# Interfaz_RTC.net
KiCad netlist of a schematic drawn in Altium Designer
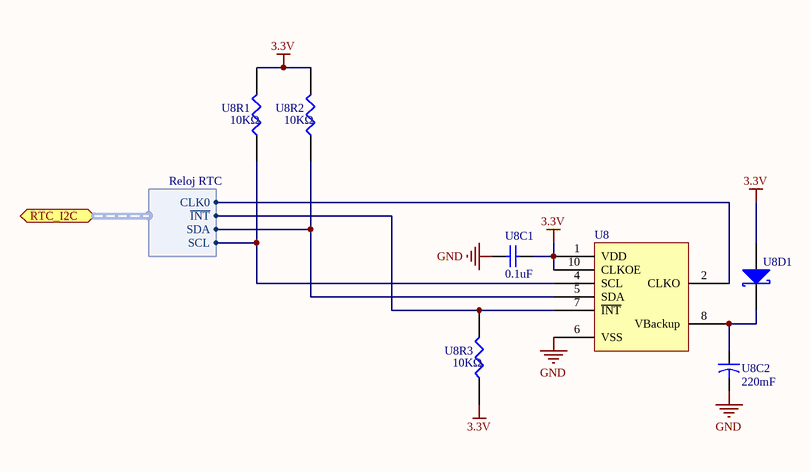
[diagram p0: Interfaz_RTC.SchDoc]

(export (version "E")
  (design (tool "Eeschema 10.0.6"))
  (components
    (comp (ref "U8")
      (value "~")
      (footprint "RV-3029-C2")
      (description "MICRO CRYSTAL - RV-3029-C2 OPTION B - REAL-TIME-CLOCK, SMD, I2C, 32.768KHZ")
      (fields
        (field (name "MANUFACTURER PART NUMBER") "RV-3029-C2")
        (field (name "MANUFACTURER") "Micro Crystal Switzerland")
      )
      (libsource (lib "EMLib1") (part "RV-3029-C2 B"))
    )
    (comp (ref "U8C1")
      (value "0.1uF")
      (footprint "0603 - CAP")
      (description "CAP CERAMIC 0.1UF, 25V, X7R, 0603")
      (fields
        (field (name "MANUFACTURER PART NUMBER") "CGJ3E2X7R1E104K080AA")
        (field (name "MANUFACTURER") "TDK Corporation")
      )
      (libsource (lib "*") (part "Cap"))
    )
    (comp (ref "U8C2")
      (value "220mF")
      (footprint "DSK-3R3H224U-HL")
      (description "CAP 220MF -20% +80% 3.3V SMD")
      (fields
        (field (name "MANUFACTURER") "Elna America")
        (field (name "MANUFACTURER PART NUMBER") "DSK-3R3H224U-HL")
      )
      (libsource (lib "Miscellaneous Devices") (part "Cap2"))
    )
    (comp (ref "U8D1")
      (value "NSR0320MW2T1G")
      (footprint "SOD-323")
      (description "DIODE SCHOTTKY 1A 20V SOD-323")
      (fields (field (name "MANUFACTURER") "On Semiconductor"))
      (libsource (lib "IR Discrete Rectifier - Schottky") (part "10MQ060N"))
    )
    (comp (ref "U8R1")
      (value "10KΩ")
      (footprint "0805-RES")
      (description "10 kOhms ±5% 0.125W, 1/8W Chip Resistor 0805")
      (fields
        (field (name "MANUFACTURER PART NUMBER") "RC0805JR-0710KL")
        (field (name "MANUFACTURER") "Yageo")
      )
      (libsource (lib "*") (part "RES1"))
    )
    (comp (ref "U8R2")
      (value "10KΩ")
      (footprint "0805-RES")
      (description "10 kOhms ±5% 0.125W, 1/8W Chip Resistor 0805")
      (fields
        (field (name "MANUFACTURER PART NUMBER") "RC0805JR-0710KL")
        (field (name "MANUFACTURER") "Yageo")
      )
      (libsource (lib "*") (part "RES1"))
    )
    (comp (ref "U8R3")
      (value "10KΩ")
      (footprint "0805-RES")
      (description "10 kOhms ±5% 0.125W, 1/8W Chip Resistor 0805")
      (fields
        (field (name "MANUFACTURER PART NUMBER") "RC0805JR-0710KL")
        (field (name "MANUFACTURER") "Yageo")
      )
      (libsource (lib "*") (part "RES1"))
    )
  )
  (nets
    (net (code "3") (name "/CLK0") (class "Default")
      (node (ref "U8") (pin "2") (pinfunction "CLKO_2") (pintype "passive"))
    )
    (net (code "4") (name "/SCL") (class "Default")
      (node (ref "U8") (pin "4") (pinfunction "SCL_4") (pintype "passive"))
      (node (ref "U8R1") (pin "1") (pinfunction "1_1") (pintype "passive"))
    )
    (net (code "5") (name "/SDA") (class "Default")
      (node (ref "U8") (pin "5") (pinfunction "SDA_5") (pintype "passive"))
      (node (ref "U8R2") (pin "1") (pinfunction "1_1") (pintype "passive"))
    )
    (net (code "7") (name "/~{INT}") (class "Default")
      (node (ref "U8") (pin "7") (pinfunction "~{INT}_7") (pintype "passive"))
      (node (ref "U8R3") (pin "2") (pinfunction "2_2") (pintype "passive"))
    )
    (net (code "8") (name "3.3V") (class "Default")
      (node (ref "U8") (pin "1") (pinfunction "VDD_1") (pintype "passive"))
      (node (ref "U8") (pin "10") (pinfunction "CLKOE_10") (pintype "passive"))
      (node (ref "U8C1") (pin "1") (pinfunction "1_1") (pintype "passive"))
      (node (ref "U8D1") (pin "1") (pinfunction "A_1") (pintype "passive"))
      (node (ref "U8R1") (pin "2") (pinfunction "2_2") (pintype "passive"))
      (node (ref "U8R2") (pin "2") (pinfunction "2_2") (pintype "passive"))
      (node (ref "U8R3") (pin "1") (pinfunction "1_1") (pintype "passive"))
    )
    (net (code "9") (name "GND") (class "Default")
      (node (ref "U8") (pin "6") (pinfunction "VSS_6") (pintype "passive"))
      (node (ref "U8C1") (pin "2") (pinfunction "2_2") (pintype "passive"))
      (node (ref "U8C2") (pin "2") (pinfunction "2_2") (pintype "passive"))
    )
    (net (code "10") (name "Net-(U8-VBackup)") (class "Default")
      (node (ref "U8") (pin "8") (pinfunction "VBackup_8") (pintype "passive"))
      (node (ref "U8C2") (pin "1") (pinfunction "1_1") (pintype "passive"))
      (node (ref "U8D1") (pin "2") (pinfunction "K_2") (pintype "passive"))
    )
    (net (code "11") (name "unconnected-(U8-NC-Pad3)") (class "Default")
      (node (ref "U8") (pin "3") (pinfunction "NC_3") (pintype "passive"))
    )
    (net (code "12") (name "unconnected-(U8-NC-Pad9)") (class "Default")
      (node (ref "U8") (pin "9") (pinfunction "NC_9") (pintype "passive"))
    )
  )
)
